# zhernakov_pwron_circuit.net
KiCad netlist of a schematic drawn in Altium Designer
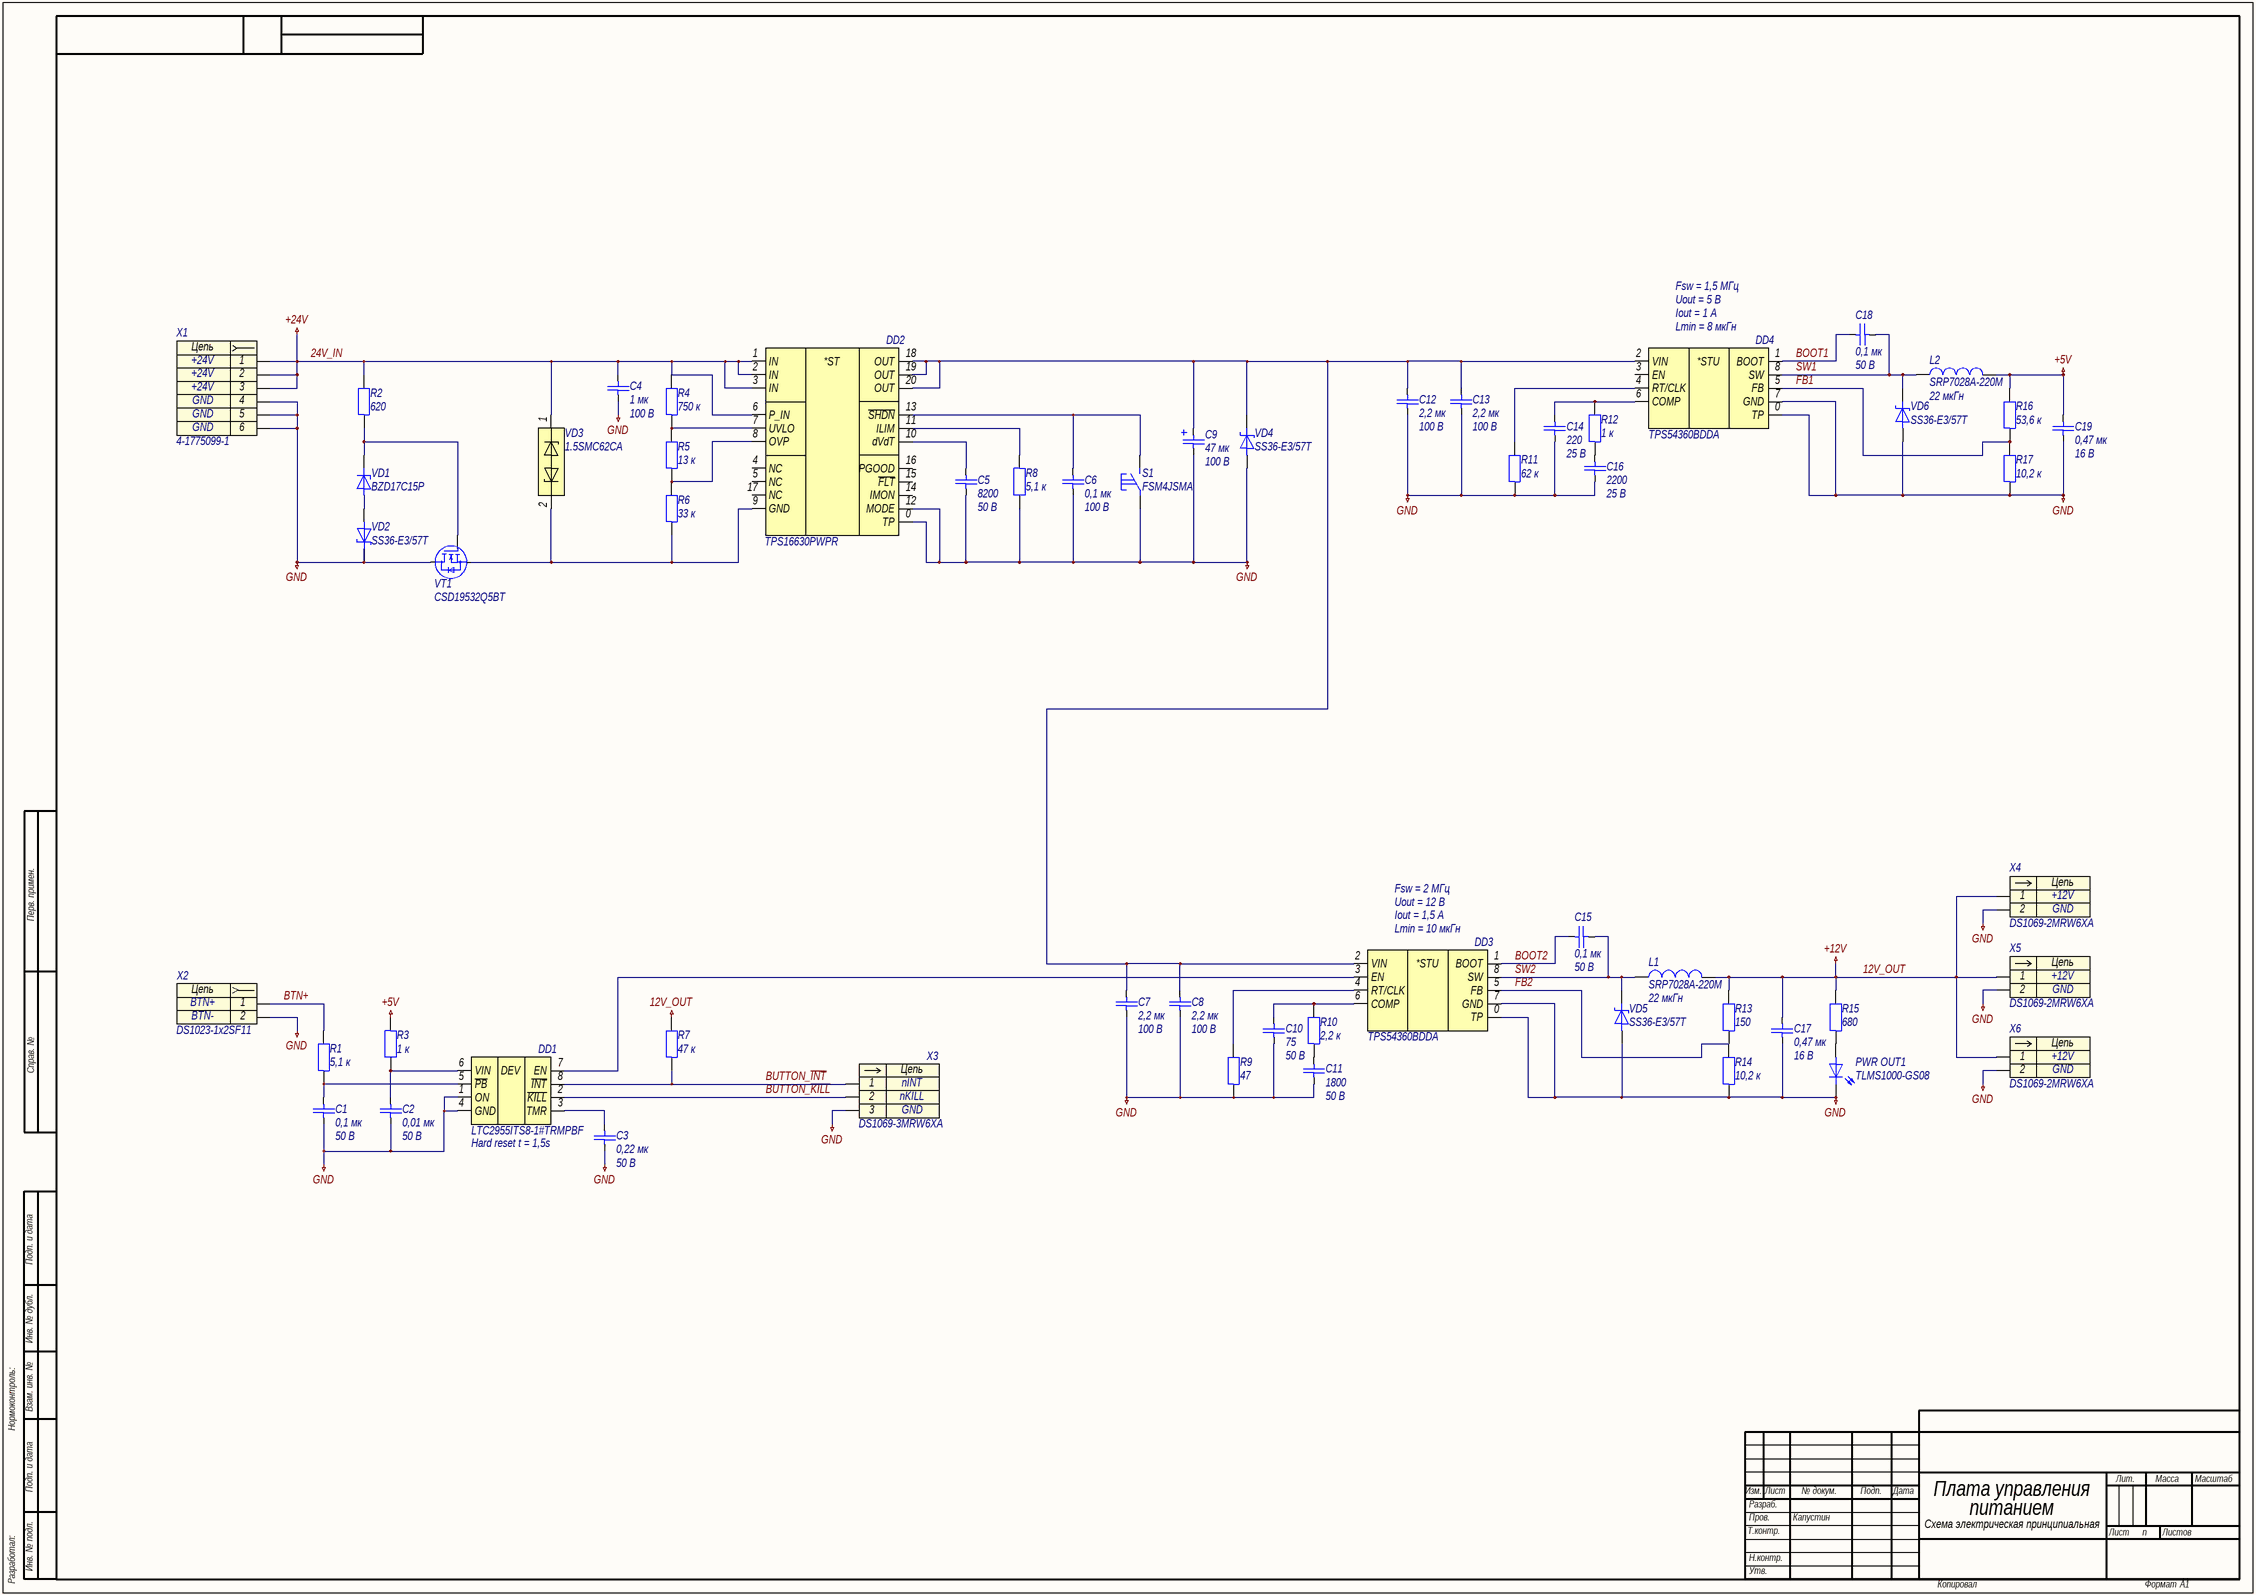
[diagram p0: zhernakov_pwron_circuit.SchDoc]

(export (version "E")
  (design (tool "Eeschema 10.0.6"))
  (components
    (comp (ref "C1")
      (value "0,1 мк")
      (footprint "C0603")
      (description "=Описание")
      (fields (field (name "НАПРЯЖЕНИЕ") "50 В"))
      (libsource (lib "Database_Students") (part "CAPACITOR-NONPOLAR"))
    )
    (comp (ref "C2")
      (value "0,01 мк")
      (footprint "C0603")
      (description "=Описание")
      (fields (field (name "НАПРЯЖЕНИЕ") "50 В"))
      (libsource (lib "Database_Students") (part "CAPACITOR-NONPOLAR"))
    )
    (comp (ref "C3")
      (value "0,22 мк")
      (footprint "C0603")
      (description "=Описание")
      (fields (field (name "НАПРЯЖЕНИЕ") "50 В"))
      (libsource (lib "Database_Students") (part "CAPACITOR-NONPOLAR"))
    )
    (comp (ref "C4")
      (value "1 мк")
      (footprint "C1206")
      (description "=Описание")
      (fields (field (name "НАПРЯЖЕНИЕ") "100 В"))
      (libsource (lib "Database_Students") (part "CAPACITOR-NONPOLAR"))
    )
    (comp (ref "C5")
      (value "8200")
      (footprint "C0402")
      (description "=Описание")
      (fields (field (name "НАПРЯЖЕНИЕ") "50 В"))
      (libsource (lib "Database_Students") (part "CAPACITOR-NONPOLAR"))
    )
    (comp (ref "C6")
      (value "0,1 мк")
      (footprint "C0603")
      (description "=Описание")
      (fields (field (name "НАПРЯЖЕНИЕ") "100 В"))
      (libsource (lib "Database_Students") (part "CAPACITOR-NONPOLAR"))
    )
    (comp (ref "C7")
      (value "2,2 мк")
      (footprint "C1206")
      (description "=Описание")
      (fields (field (name "НАПРЯЖЕНИЕ") "100 В"))
      (libsource (lib "Database_Students") (part "CAPACITOR-NONPOLAR"))
    )
    (comp (ref "C8")
      (value "2,2 мк")
      (footprint "C1206")
      (description "=Описание")
      (fields (field (name "НАПРЯЖЕНИЕ") "100 В"))
      (libsource (lib "Database_Students") (part "CAPACITOR-NONPOLAR"))
    )
    (comp (ref "C9")
      (value "47 мк")
      (footprint "CAPAE-1000X1000X1200")
      (description "=Описание")
      (fields (field (name "НАПРЯЖЕНИЕ") "100 В"))
      (libsource (lib "Database_Students") (part "CAPACITOR-POLAR"))
    )
    (comp (ref "C10")
      (value "75")
      (footprint "C0402")
      (description "=Описание")
      (fields (field (name "НАПРЯЖЕНИЕ") "50 В"))
      (libsource (lib "Database_Students") (part "CAPACITOR-NONPOLAR"))
    )
    (comp (ref "C11")
      (value "1800")
      (footprint "C0402")
      (description "=Описание")
      (fields (field (name "НАПРЯЖЕНИЕ") "50 В"))
      (libsource (lib "Database_Students") (part "CAPACITOR-NONPOLAR"))
    )
    (comp (ref "C12")
      (value "2,2 мк")
      (footprint "C1206")
      (description "=Описание")
      (fields (field (name "НАПРЯЖЕНИЕ") "100 В"))
      (libsource (lib "Database_Students") (part "CAPACITOR-NONPOLAR"))
    )
    (comp (ref "C13")
      (value "2,2 мк")
      (footprint "C1206")
      (description "=Описание")
      (fields (field (name "НАПРЯЖЕНИЕ") "100 В"))
      (libsource (lib "Database_Students") (part "CAPACITOR-NONPOLAR"))
    )
    (comp (ref "C14")
      (value "220")
      (footprint "C0603")
      (description "=Описание")
      (fields (field (name "НАПРЯЖЕНИЕ") "25 В"))
      (libsource (lib "Database_Students") (part "CAPACITOR-NONPOLAR"))
    )
    (comp (ref "C15")
      (value "0,1 мк")
      (footprint "C0603")
      (description "=Описание")
      (fields (field (name "НАПРЯЖЕНИЕ") "50 В"))
      (libsource (lib "Database_Students") (part "CAPACITOR-NONPOLAR"))
    )
    (comp (ref "C16")
      (value "2200")
      (footprint "C0201")
      (description "=Описание")
      (fields (field (name "НАПРЯЖЕНИЕ") "25 В"))
      (libsource (lib "Database_Students") (part "CAPACITOR-NONPOLAR"))
    )
    (comp (ref "C17")
      (value "0,47 мк")
      (footprint "C0603")
      (description "=Описание")
      (fields (field (name "НАПРЯЖЕНИЕ") "16 В"))
      (libsource (lib "Database_Students") (part "CAPACITOR-NONPOLAR"))
    )
    (comp (ref "C18")
      (value "0,1 мк")
      (footprint "C0603")
      (description "=Описание")
      (fields (field (name "НАПРЯЖЕНИЕ") "50 В"))
      (libsource (lib "Database_Students") (part "CAPACITOR-NONPOLAR"))
    )
    (comp (ref "C19")
      (value "0,47 мк")
      (footprint "C0603")
      (description "=Описание")
      (fields (field (name "НАПРЯЖЕНИЕ") "16 В"))
      (libsource (lib "Database_Students") (part "CAPACITOR-NONPOLAR"))
    )
    (comp (ref "DD1")
      (value "LTC2955ITS8-1#TRMPBF")
      (footprint "SOT-23-8-P65-290X280X100")
      (description "=Описание")
      (libsource (lib "Database_Students") (part "LTC2955ITS8-1#TRMPBF"))
    )
    (comp (ref "DD2")
      (value "TPS16630PWPR")
      (footprint "HTSSOP-20-P65-650X440X120-L63X25-T296X296")
      (description "=Описание")
      (libsource (lib "Database_Students") (part "TPS16630PWPR"))
    )
    (comp (ref "DD3")
      (value "TPS54360BDDA")
      (footprint "HSOIC-8-P127-490X390X170-L84X41-T310X240")
      (description "=Описание")
      (libsource (lib "Database_Students") (part "TPS54360BDDA"))
    )
    (comp (ref "DD4")
      (value "TPS54360BDDA")
      (footprint "HSOIC-8-P127-490X390X170-L84X41-T310X240")
      (description "=Описание")
      (libsource (lib "Database_Students") (part "TPS54360BDDA"))
    )
    (comp (ref "L1")
      (value "SRP7028A-220M")
      (footprint "SRP-2-730X660X280")
      (description "=Описание")
      (fields (field (name "ИНДУКТИВНОСТЬ") "22 мкГн"))
      (libsource (lib "Database_Students") (part "INDUCTOR-COMMON"))
    )
    (comp (ref "L2")
      (value "SRP7028A-220M")
      (footprint "SRP-2-730X660X280")
      (description "=Описание")
      (fields (field (name "ИНДУКТИВНОСТЬ") "22 мкГн"))
      (libsource (lib "Database_Students") (part "INDUCTOR-COMMON"))
    )
    (comp (ref "PWR OUT1")
      (value "TLMS1000-GS08")
      (footprint "HL0603")
      (description "=Описание")
      (libsource (lib "Database_Students") (part "HL-COMMON"))
    )
    (comp (ref "R1")
      (value "5,1 к")
      (footprint "R0603")
      (description "=Описание")
      (libsource (lib "Database_Students") (part "RESISTOR-COMMON"))
    )
    (comp (ref "R2")
      (value "620")
      (footprint "R0603")
      (description "=Описание")
      (libsource (lib "Database_Students") (part "RESISTOR-COMMON"))
    )
    (comp (ref "R3")
      (value "1 к")
      (footprint "R0603")
      (description "=Описание")
      (libsource (lib "Database_Students") (part "RESISTOR-COMMON"))
    )
    (comp (ref "R4")
      (value "750 к")
      (footprint "R0603")
      (description "=Описание")
      (libsource (lib "Database_Students") (part "RESISTOR-COMMON"))
    )
    (comp (ref "R5")
      (value "13 к")
      (footprint "R0603")
      (description "=Описание")
      (libsource (lib "Database_Students") (part "RESISTOR-COMMON"))
    )
    (comp (ref "R6")
      (value "33 к")
      (footprint "R0603")
      (description "=Описание")
      (libsource (lib "Database_Students") (part "RESISTOR-COMMON"))
    )
    (comp (ref "R7")
      (value "47 к")
      (footprint "R0603")
      (description "=Описание")
      (libsource (lib "Database_Students") (part "RESISTOR-COMMON"))
    )
    (comp (ref "R8")
      (value "5,1 к")
      (footprint "R0603")
      (description "=Описание")
      (libsource (lib "Database_Students") (part "R-COMMON"))
    )
    (comp (ref "R9")
      (value "47")
      (footprint "R0603")
      (description "=Описание")
      (libsource (lib "Database_Students") (part "RESISTOR-COMMON"))
    )
    (comp (ref "R10")
      (value "2,2 к")
      (footprint "R0603")
      (description "=Описание")
      (libsource (lib "Database_Students") (part "RESISTOR-COMMON"))
    )
    (comp (ref "R11")
      (value "62 к")
      (footprint "R0603")
      (description "=Описание")
      (libsource (lib "Database_Students") (part "RESISTOR-COMMON"))
    )
    (comp (ref "R12")
      (value "1 к")
      (footprint "R0603")
      (description "=Описание")
      (libsource (lib "Database_Students") (part "RESISTOR-COMMON"))
    )
    (comp (ref "R13")
      (value "150")
      (footprint "R0603")
      (description "=Описание")
      (libsource (lib "Database_Students") (part "RESISTOR-COMMON"))
    )
    (comp (ref "R14")
      (value "10,2 к")
      (footprint "R0603")
      (description "=Описание")
      (libsource (lib "Database_Students") (part "R-COMMON"))
    )
    (comp (ref "R15")
      (value "680")
      (footprint "R0603")
      (description "=Описание")
      (libsource (lib "Database_Students") (part "RESISTOR-COMMON"))
    )
    (comp (ref "R16")
      (value "53,6 к")
      (footprint "R0603")
      (description "=Описание")
      (libsource (lib "Database_Students") (part "R-COMMON"))
    )
    (comp (ref "R17")
      (value "10,2 к")
      (footprint "R0603")
      (description "=Описание")
      (libsource (lib "Database_Students") (part "R-COMMON"))
    )
    (comp (ref "S1")
      (value "FSM4JSMA")
      (footprint "FSM4JSMA")
      (description "=Описание")
      (libsource (lib "Database_Students") (part "BUTTON"))
    )
    (comp (ref "VD1")
      (value "BZD17C15P")
      (footprint "DO-219AB-280X180X108")
      (description "=Описание")
      (libsource (lib "Database_Students") (part "DIODE-ZENER"))
    )
    (comp (ref "VD2")
      (value "SS36-E3/57T")
      (footprint "DO-214AB-790X590X262")
      (description "=Описание")
      (libsource (lib "Database_Students") (part "DIODE-SCHOTTKY"))
    )
    (comp (ref "VD3")
      (value "1.5SMC62CA")
      (footprint "DO-214AB-790X590X262")
      (description "=Описание")
      (libsource (lib "Database_Students") (part "ZENER-BI-DIRECTIONAL"))
    )
    (comp (ref "VD4")
      (value "SS36-E3/57T")
      (footprint "DO-214AB-790X590X262")
      (description "=Описание")
      (libsource (lib "Database_Students") (part "DIODE-SCHOTTKY"))
    )
    (comp (ref "VD5")
      (value "SS36-E3/57T")
      (footprint "DO-214AB-790X590X262")
      (description "=Описание")
      (libsource (lib "Database_Students") (part "DIODE-SCHOTTKY"))
    )
    (comp (ref "VD6")
      (value "SS36-E3/57T")
      (footprint "DO-214AB-790X590X262")
      (description "=Описание")
      (libsource (lib "Database_Students") (part "DIODE-SCHOTTKY"))
    )
    (comp (ref "VT1")
      (value "CSD19532Q5BT")
      (footprint "VSONP-8-P127-600X500X105")
      (description "=Описание")
      (libsource (lib "Database_Students") (part "MOSFET-N-DIODE"))
    )
    (comp (ref "X1")
      (value "4-1775099-1")
      (footprint "4-1775099-1")
      (description "=Описание")
      (libsource (lib "Database_Students") (part "HEADER-6-SCT"))
    )
    (comp (ref "X2")
      (value "DS1023-1x2SF11")
      (footprint "DS1023-1X2SF11")
      (description "=Описание")
      (libsource (lib "Database_Students") (part "HEADER-2-SCT"))
    )
    (comp (ref "X3")
      (value "DS1069-3MRW6XA")
      (footprint "DS1069-3MRW6XA")
      (description "=Описание")
      (libsource (lib "Database_Students") (part "HEADER-3-PLG"))
    )
    (comp (ref "X4")
      (value "DS1069-2MRW6XA")
      (footprint "DS1069-2MRW6XA")
      (description "=Описание")
      (libsource (lib "Database_Students") (part "HEADER-2-PLG"))
    )
    (comp (ref "X5")
      (value "DS1069-2MRW6XA")
      (footprint "DS1069-2MRW6XA")
      (description "=Описание")
      (libsource (lib "Database_Students") (part "HEADER-2-PLG"))
    )
    (comp (ref "X6")
      (value "DS1069-2MRW6XA")
      (footprint "DS1069-2MRW6XA")
      (description "=Описание")
      (libsource (lib "Database_Students") (part "HEADER-2-PLG"))
    )
  )
  (nets
    (net (code "1") (name "+5V") (class "Default")
      (node (ref "C19") (pin "1") (pinfunction "1_1") (pintype "passive"))
      (node (ref "L2") (pin "2") (pinfunction "2_2") (pintype "passive"))
      (node (ref "R16") (pin "2") (pinfunction "2_2") (pintype "passive"))
      (node (ref "R3") (pin "1") (pinfunction "1_1") (pintype "passive"))
    )
    (net (code "2") (name "+12V") (class "Default")
      (node (ref "C17") (pin "1") (pinfunction "1_1") (pintype "passive"))
      (node (ref "L1") (pin "2") (pinfunction "2_2") (pintype "passive"))
      (node (ref "R13") (pin "2") (pinfunction "2_2") (pintype "passive"))
      (node (ref "R15") (pin "2") (pinfunction "2_2") (pintype "passive"))
      (node (ref "R7") (pin "2") (pinfunction "2_2") (pintype "passive"))
      (node (ref "X4") (pin "1") (pinfunction "1_1") (pintype "passive"))
      (node (ref "X5") (pin "1") (pinfunction "1_1") (pintype "passive"))
      (node (ref "X6") (pin "1") (pinfunction "1_1") (pintype "passive"))
    )
    (net (code "3") (name "+24V") (class "Default")
      (node (ref "C4") (pin "1") (pinfunction "1_1") (pintype "passive"))
      (node (ref "DD2") (pin "1") (pinfunction "IN_1") (pintype "passive"))
      (node (ref "DD2") (pin "2") (pinfunction "IN_2") (pintype "passive"))
      (node (ref "DD2") (pin "3") (pinfunction "IN_3") (pintype "passive"))
      (node (ref "DD2") (pin "6") (pinfunction "P_IN_6") (pintype "passive"))
      (node (ref "R2") (pin "2") (pinfunction "2_2") (pintype "passive"))
      (node (ref "R4") (pin "2") (pinfunction "2_2") (pintype "passive"))
      (node (ref "VD3") (pin "1") (pinfunction "1_1") (pintype "passive"))
      (node (ref "X1") (pin "1") (pinfunction "1_1") (pintype "passive"))
      (node (ref "X1") (pin "2") (pinfunction "2_2") (pintype "passive"))
      (node (ref "X1") (pin "3") (pinfunction "3_3") (pintype "passive"))
    )
    (net (code "4") (name "/BOOT1") (class "Default")
      (node (ref "C18") (pin "1") (pinfunction "1_1") (pintype "passive"))
      (node (ref "DD4") (pin "1") (pinfunction "BOOT_1") (pintype "passive"))
    )
    (net (code "5") (name "/BOOT2") (class "Default")
      (node (ref "C15") (pin "1") (pinfunction "1_1") (pintype "passive"))
      (node (ref "DD3") (pin "1") (pinfunction "BOOT_1") (pintype "passive"))
    )
    (net (code "6") (name "/BTN+") (class "Default")
      (node (ref "R1") (pin "2") (pinfunction "2_2") (pintype "passive"))
      (node (ref "X2") (pin "1") (pinfunction "1_1") (pintype "passive"))
    )
    (net (code "7") (name "/BUTTON_~{INT}") (class "Default")
      (node (ref "DD1") (pin "8") (pinfunction "~{INT}_8") (pintype "passive"))
      (node (ref "R7") (pin "1") (pinfunction "1_1") (pintype "passive"))
      (node (ref "X3") (pin "1") (pinfunction "1_1") (pintype "passive"))
    )
    (net (code "8") (name "/BUTTON_~{KILL}") (class "Default")
      (node (ref "DD1") (pin "2") (pinfunction "~{KILL}_2") (pintype "passive"))
      (node (ref "X3") (pin "2") (pinfunction "2_2") (pintype "passive"))
    )
    (net (code "9") (name "/FB1") (class "Default")
      (node (ref "DD4") (pin "5") (pinfunction "FB_5") (pintype "passive"))
      (node (ref "R16") (pin "1") (pinfunction "1_1") (pintype "passive"))
      (node (ref "R17") (pin "2") (pinfunction "2_2") (pintype "passive"))
    )
    (net (code "10") (name "/FB2") (class "Default")
      (node (ref "DD3") (pin "5") (pinfunction "FB_5") (pintype "passive"))
      (node (ref "R13") (pin "1") (pinfunction "1_1") (pintype "passive"))
      (node (ref "R14") (pin "2") (pinfunction "2_2") (pintype "passive"))
    )
    (net (code "11") (name "/SW1") (class "Default")
      (node (ref "C18") (pin "2") (pinfunction "2_2") (pintype "passive"))
      (node (ref "DD4") (pin "8") (pinfunction "SW_8") (pintype "passive"))
      (node (ref "L2") (pin "1") (pinfunction "1_1") (pintype "passive"))
      (node (ref "VD6") (pin "1") (pinfunction "1_1") (pintype "passive"))
    )
    (net (code "12") (name "/SW2") (class "Default")
      (node (ref "C15") (pin "2") (pinfunction "2_2") (pintype "passive"))
      (node (ref "DD3") (pin "8") (pinfunction "SW_8") (pintype "passive"))
      (node (ref "L1") (pin "1") (pinfunction "1_1") (pintype "passive"))
      (node (ref "VD5") (pin "1") (pinfunction "1_1") (pintype "passive"))
    )
    (net (code "13") (name "GND") (class "Default")
      (node (ref "C1") (pin "2") (pinfunction "2_2") (pintype "passive"))
      (node (ref "C10") (pin "2") (pinfunction "2_2") (pintype "passive"))
      (node (ref "C11") (pin "2") (pinfunction "2_2") (pintype "passive"))
      (node (ref "C12") (pin "2") (pinfunction "2_2") (pintype "passive"))
      (node (ref "C13") (pin "2") (pinfunction "2_2") (pintype "passive"))
      (node (ref "C14") (pin "2") (pinfunction "2_2") (pintype "passive"))
      (node (ref "C16") (pin "2") (pinfunction "2_2") (pintype "passive"))
      (node (ref "C17") (pin "2") (pinfunction "2_2") (pintype "passive"))
      (node (ref "C19") (pin "2") (pinfunction "2_2") (pintype "passive"))
      (node (ref "C2") (pin "2") (pinfunction "2_2") (pintype "passive"))
      (node (ref "C3") (pin "2") (pinfunction "2_2") (pintype "passive"))
      (node (ref "C4") (pin "2") (pinfunction "2_2") (pintype "passive"))
      (node (ref "C5") (pin "2") (pinfunction "2_2") (pintype "passive"))
      (node (ref "C6") (pin "2") (pinfunction "2_2") (pintype "passive"))
      (node (ref "C7") (pin "2") (pinfunction "2_2") (pintype "passive"))
      (node (ref "C8") (pin "2") (pinfunction "2_2") (pintype "passive"))
      (node (ref "C9") (pin "2") (pinfunction "2_2") (pintype "passive"))
      (node (ref "DD1") (pin "1") (pinfunction "ON_1") (pintype "passive"))
      (node (ref "DD1") (pin "4") (pinfunction "GND_4") (pintype "passive"))
      (node (ref "DD2") (pin "0") (pinfunction "TP_0") (pintype "passive"))
      (node (ref "DD2") (pin "12") (pinfunction "MODE_12") (pintype "passive"))
      (node (ref "DD3") (pin "0") (pinfunction "TP_0") (pintype "passive"))
      (node (ref "DD3") (pin "7") (pinfunction "GND_7") (pintype "passive"))
      (node (ref "DD4") (pin "0") (pinfunction "TP_0") (pintype "passive"))
      (node (ref "DD4") (pin "7") (pinfunction "GND_7") (pintype "passive"))
      (node (ref "PWR OUT1") (pin "1") (pinfunction "1_1") (pintype "passive"))
      (node (ref "R11") (pin "1") (pinfunction "1_1") (pintype "passive"))
      (node (ref "R14") (pin "1") (pinfunction "1_1") (pintype "passive"))
      (node (ref "R17") (pin "1") (pinfunction "1_1") (pintype "passive"))
      (node (ref "R8") (pin "2") (pinfunction "2_2") (pintype "passive"))
      (node (ref "R9") (pin "1") (pinfunction "1_1") (pintype "passive"))
      (node (ref "S1") (pin "1") (pinfunction "1_1") (pintype "passive"))
      (node (ref "VD2") (pin "1") (pinfunction "1_1") (pintype "passive"))
      (node (ref "VD4") (pin "2") (pinfunction "2_2") (pintype "passive"))
      (node (ref "VD5") (pin "2") (pinfunction "2_2") (pintype "passive"))
      (node (ref "VD6") (pin "2") (pinfunction "2_2") (pintype "passive"))
      (node (ref "VT1") (pin "D") (pinfunction "D_D") (pintype "passive"))
      (node (ref "X1") (pin "4") (pinfunction "4_4") (pintype "passive"))
      (node (ref "X1") (pin "5") (pinfunction "5_5") (pintype "passive"))
      (node (ref "X1") (pin "6") (pinfunction "6_6") (pintype "passive"))
      (node (ref "X2") (pin "2") (pinfunction "2_2") (pintype "passive"))
      (node (ref "X3") (pin "3") (pinfunction "3_3") (pintype "passive"))
      (node (ref "X4") (pin "2") (pinfunction "2_2") (pintype "passive"))
      (node (ref "X5") (pin "2") (pinfunction "2_2") (pintype "passive"))
      (node (ref "X6") (pin "2") (pinfunction "2_2") (pintype "passive"))
    )
    (net (code "14") (name "Net-(C11-Pad1)") (class "Default")
      (node (ref "C11") (pin "1") (pinfunction "1_1") (pintype "passive"))
      (node (ref "R10") (pin "1") (pinfunction "1_1") (pintype "passive"))
    )
    (net (code "15") (name "Net-(C16-Pad1)") (class "Default")
      (node (ref "C16") (pin "1") (pinfunction "1_1") (pintype "passive"))
      (node (ref "R12") (pin "1") (pinfunction "1_1") (pintype "passive"))
    )
    (net (code "16") (name "Net-(DD1-EN)") (class "Default")
      (node (ref "DD1") (pin "7") (pinfunction "EN_7") (pintype "passive"))
      (node (ref "DD3") (pin "3") (pinfunction "EN_3") (pintype "passive"))
    )
    (net (code "17") (name "Net-(DD1-TMR)") (class "Default")
      (node (ref "C3") (pin "1") (pinfunction "1_1") (pintype "passive"))
      (node (ref "DD1") (pin "3") (pinfunction "TMR_3") (pintype "passive"))
    )
    (net (code "18") (name "Net-(DD1-VIN)") (class "Default")
      (node (ref "C2") (pin "1") (pinfunction "1_1") (pintype "passive"))
      (node (ref "DD1") (pin "6") (pinfunction "VIN_6") (pintype "passive"))
      (node (ref "R3") (pin "2") (pinfunction "2_2") (pintype "passive"))
    )
    (net (code "19") (name "Net-(DD1-~{PB})") (class "Default")
      (node (ref "C1") (pin "1") (pinfunction "1_1") (pintype "passive"))
      (node (ref "DD1") (pin "5") (pinfunction "~{PB}_5") (pintype "passive"))
      (node (ref "R1") (pin "1") (pinfunction "1_1") (pintype "passive"))
    )
    (net (code "20") (name "Net-(DD2-GND)") (class "Default")
      (node (ref "DD2") (pin "9") (pinfunction "GND_9") (pintype "passive"))
      (node (ref "R6") (pin "1") (pinfunction "1_1") (pintype "passive"))
      (node (ref "VD3") (pin "2") (pinfunction "2_2") (pintype "passive"))
      (node (ref "VT1") (pin "S") (pinfunction "S_S") (pintype "passive"))
    )
    (net (code "21") (name "Net-(DD2-ILIM)") (class "Default")
      (node (ref "DD2") (pin "11") (pinfunction "ILIM_11") (pintype "passive"))
      (node (ref "R8") (pin "1") (pinfunction "1_1") (pintype "passive"))
    )
    (net (code "22") (name "Net-(DD2-OVP)") (class "Default")
      (node (ref "DD2") (pin "8") (pinfunction "OVP_8") (pintype "passive"))
      (node (ref "R5") (pin "1") (pinfunction "1_1") (pintype "passive"))
      (node (ref "R6") (pin "2") (pinfunction "2_2") (pintype "passive"))
    )
    (net (code "23") (name "Net-(DD2-UVLO)") (class "Default")
      (node (ref "DD2") (pin "7") (pinfunction "UVLO_7") (pintype "passive"))
      (node (ref "R4") (pin "1") (pinfunction "1_1") (pintype "passive"))
      (node (ref "R5") (pin "2") (pinfunction "2_2") (pintype "passive"))
    )
    (net (code "24") (name "Net-(DD2-dVdT)") (class "Default")
      (node (ref "C5") (pin "1") (pinfunction "1_1") (pintype "passive"))
      (node (ref "DD2") (pin "10") (pinfunction "dVdT_10") (pintype "passive"))
    )
    (net (code "25") (name "Net-(DD2-~{SHDN})") (class "Default")
      (node (ref "C6") (pin "1") (pinfunction "1_1") (pintype "passive"))
      (node (ref "DD2") (pin "13") (pinfunction "~{SHDN}_13") (pintype "passive"))
      (node (ref "S1") (pin "2") (pinfunction "2_2") (pintype "passive"))
    )
    (net (code "26") (name "Net-(DD3-COMP)") (class "Default")
      (node (ref "C10") (pin "1") (pinfunction "1_1") (pintype "passive"))
      (node (ref "DD3") (pin "6") (pinfunction "COMP_6") (pintype "passive"))
      (node (ref "R10") (pin "2") (pinfunction "2_2") (pintype "passive"))
    )
    (net (code "27") (name "Net-(DD3-RT{slash}CLK)") (class "Default")
      (node (ref "DD3") (pin "4") (pinfunction "RT/CLK_4") (pintype "passive"))
      (node (ref "R9") (pin "2") (pinfunction "2_2") (pintype "passive"))
    )
    (net (code "28") (name "Net-(DD3-VIN)") (class "Default")
      (node (ref "C12") (pin "1") (pinfunction "1_1") (pintype "passive"))
      (node (ref "C13") (pin "1") (pinfunction "1_1") (pintype "passive"))
      (node (ref "C7") (pin "1") (pinfunction "1_1") (pintype "passive"))
      (node (ref "C8") (pin "1") (pinfunction "1_1") (pintype "passive"))
      (node (ref "C9") (pin "1") (pinfunction "1_1") (pintype "passive"))
      (node (ref "DD2") (pin "18") (pinfunction "OUT_18") (pintype "passive"))
      (node (ref "DD2") (pin "19") (pinfunction "OUT_19") (pintype "passive"))
      (node (ref "DD2") (pin "20") (pinfunction "OUT_20") (pintype "passive"))
      (node (ref "DD3") (pin "2") (pinfunction "VIN_2") (pintype "passive"))
      (node (ref "DD4") (pin "2") (pinfunction "VIN_2") (pintype "passive"))
      (node (ref "VD4") (pin "1") (pinfunction "1_1") (pintype "passive"))
    )
    (net (code "29") (name "Net-(DD4-COMP)") (class "Default")
      (node (ref "C14") (pin "1") (pinfunction "1_1") (pintype "passive"))
      (node (ref "DD4") (pin "6") (pinfunction "COMP_6") (pintype "passive"))
      (node (ref "R12") (pin "2") (pinfunction "2_2") (pintype "passive"))
    )
    (net (code "30") (name "Net-(DD4-RT{slash}CLK)") (class "Default")
      (node (ref "DD4") (pin "4") (pinfunction "RT/CLK_4") (pintype "passive"))
      (node (ref "R11") (pin "2") (pinfunction "2_2") (pintype "passive"))
    )
    (net (code "31") (name "Net-(PWR OUT1-Pad2)") (class "Default")
      (node (ref "PWR OUT1") (pin "2") (pinfunction "2_2") (pintype "passive"))
      (node (ref "R15") (pin "1") (pinfunction "1_1") (pintype "passive"))
    )
    (net (code "32") (name "Net-(R2-Pad1)") (class "Default")
      (node (ref "R2") (pin "1") (pinfunction "1_1") (pintype "passive"))
      (node (ref "VD1") (pin "1") (pinfunction "1_1") (pintype "passive"))
      (node (ref "VT1") (pin "G") (pinfunction "G_G") (pintype "passive"))
    )
    (net (code "33") (name "Net-(VD1-Pad2)") (class "Default")
      (node (ref "VD1") (pin "2") (pinfunction "2_2") (pintype "passive"))
      (node (ref "VD2") (pin "2") (pinfunction "2_2") (pintype "passive"))
    )
    (net (code "34") (name "unconnected-(DD2-IMON-Pad14)") (class "Default")
      (node (ref "DD2") (pin "14") (pinfunction "IMON_14") (pintype "passive"))
    )
    (net (code "35") (name "unconnected-(DD2-NC-Pad4)") (class "Default")
      (node (ref "DD2") (pin "4") (pinfunction "NC_4") (pintype "passive"))
    )
    (net (code "36") (name "unconnected-(DD2-NC-Pad5)") (class "Default")
      (node (ref "DD2") (pin "5") (pinfunction "NC_5") (pintype "passive"))
    )
    (net (code "37") (name "unconnected-(DD2-NC-Pad17)") (class "Default")
      (node (ref "DD2") (pin "17") (pinfunction "NC_17") (pintype "passive"))
    )
    (net (code "38") (name "unconnected-(DD2-PGOOD-Pad16)") (class "Default")
      (node (ref "DD2") (pin "16") (pinfunction "PGOOD_16") (pintype "passive"))
    )
    (net (code "39") (name "unconnected-(DD2-~{FLT}-Pad15)") (class "Default")
      (node (ref "DD2") (pin "15") (pinfunction "~{FLT}_15") (pintype "passive"))
    )
    (net (code "40") (name "unconnected-(DD4-EN-Pad3)") (class "Default")
      (node (ref "DD4") (pin "3") (pinfunction "EN_3") (pintype "passive"))
    )
  )
)
